# emitter.net
KiCad netlist of a schematic drawn in EAGLE
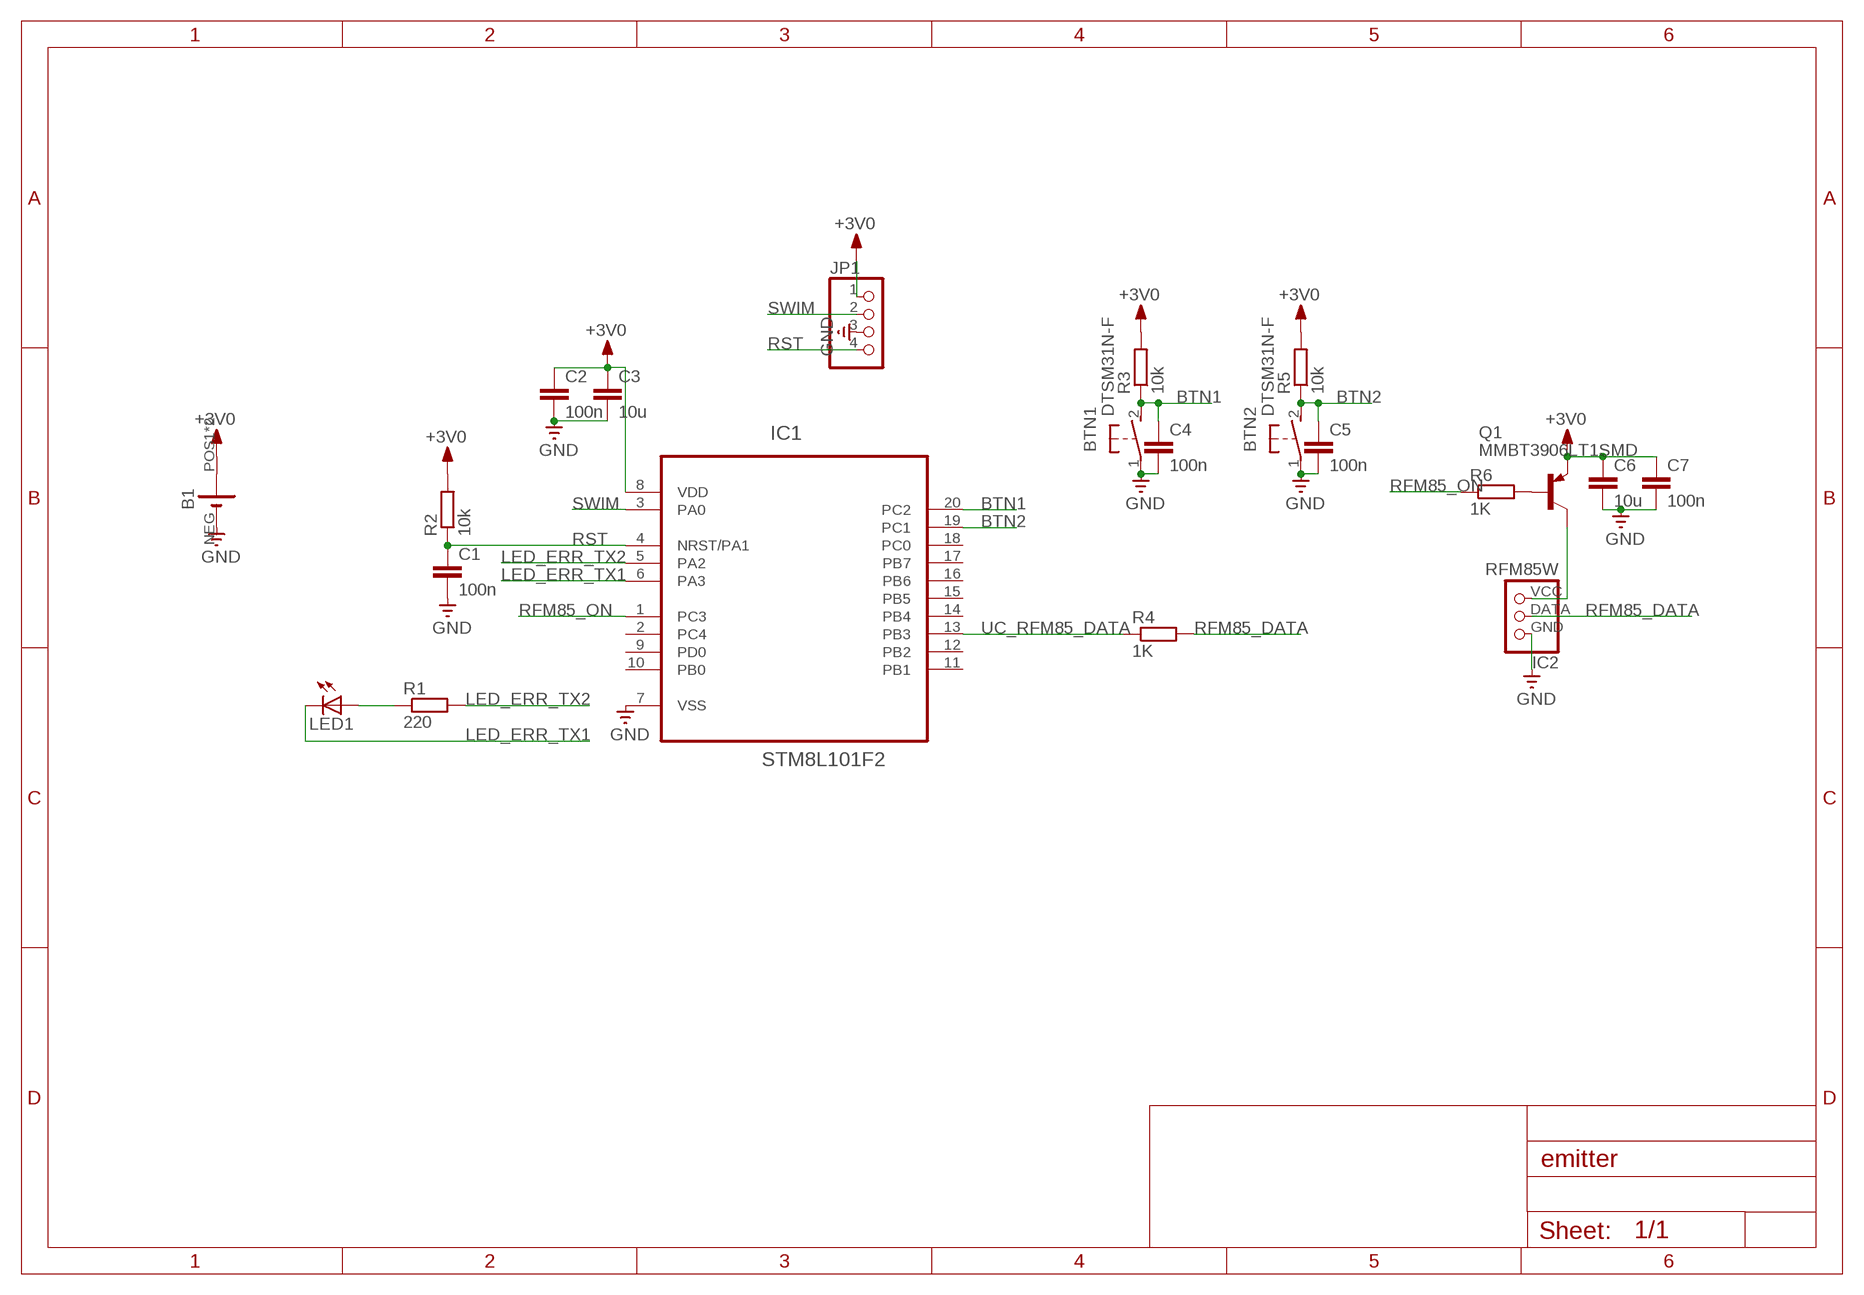
[diagram p0: schematic, sheet 1]

(export (version "E")
  (design (tool "Eeschema 10.0.6"))
  (components
    (comp (ref "B1")
      (value "CR2032_HOLDER_BC-2003")
      (footprint "eagle-import:CR2032_HOLDER_BC-2003")
      (libsource (lib "eagle-import") (part "CR2032_HOLDER_BC-2003"))
    )
    (comp (ref "BTN1")
      (value "DTSM31N-F")
      (footprint "eagle-import:DTSM31N-F")
      (libsource (lib "eagle-import") (part "DTSM31N-F"))
    )
    (comp (ref "BTN2")
      (value "DTSM31N-F")
      (footprint "eagle-import:DTSM31N-F")
      (libsource (lib "eagle-import") (part "DTSM31N-F"))
    )
    (comp (ref "C1")
      (value "100n")
      (footprint "eagle-import:C0603K")
      (libsource (lib "eagle-import") (part "C-EUC0603K"))
    )
    (comp (ref "C2")
      (value "100n")
      (footprint "eagle-import:C0603K")
      (libsource (lib "eagle-import") (part "C-EUC0603K"))
    )
    (comp (ref "C3")
      (value "10u")
      (footprint "eagle-import:C0805K")
      (libsource (lib "eagle-import") (part "C-EUC0805K"))
    )
    (comp (ref "C4")
      (value "100n")
      (footprint "eagle-import:C0603K")
      (libsource (lib "eagle-import") (part "C-EUC0603K"))
    )
    (comp (ref "C5")
      (value "100n")
      (footprint "eagle-import:C0603K")
      (libsource (lib "eagle-import") (part "C-EUC0603K"))
    )
    (comp (ref "C6")
      (value "10u")
      (footprint "eagle-import:C0805K")
      (libsource (lib "eagle-import") (part "C-EUC0805K"))
    )
    (comp (ref "C7")
      (value "100n")
      (footprint "eagle-import:C0603K")
      (libsource (lib "eagle-import") (part "C-EUC0603K"))
    )
    (comp (ref "IC1")
      (value "STM8L101F2")
      (footprint "eagle-import:TSSOP20")
      (libsource (lib "eagle-import") (part "STM8L101F2"))
    )
    (comp (ref "IC2")
      (value "RFM85W")
      (footprint "eagle-import:RFM85W_CON")
      (libsource (lib "eagle-import") (part "RFM85W"))
    )
    (comp (ref "JP1")
      (value "PINHD-1X4")
      (footprint "eagle-import:1X04")
      (libsource (lib "eagle-import") (part "PINHD-1X4"))
    )
    (comp (ref "LED1")
      (value "LED3MM")
      (footprint "eagle-import:LED3MM")
      (libsource (lib "eagle-import") (part "LED3MM"))
    )
    (comp (ref "Q1")
      (value "MMBT3906LT1SMD")
      (footprint "eagle-import:SOT23-BEC")
      (libsource (lib "eagle-import") (part "MMBT3906SMDLT1"))
    )
    (comp (ref "R1")
      (value "220")
      (footprint "eagle-import:R0603")
      (libsource (lib "eagle-import") (part "R-EU_R0603"))
    )
    (comp (ref "R2")
      (value "10k")
      (footprint "eagle-import:R0603")
      (libsource (lib "eagle-import") (part "R-EU_R0603"))
    )
    (comp (ref "R3")
      (value "10k")
      (footprint "eagle-import:R0603")
      (libsource (lib "eagle-import") (part "R-EU_R0603"))
    )
    (comp (ref "R4")
      (value "1K")
      (footprint "eagle-import:R0603")
      (libsource (lib "eagle-import") (part "R-EU_R0603"))
    )
    (comp (ref "R5")
      (value "10k")
      (footprint "eagle-import:R0603")
      (libsource (lib "eagle-import") (part "R-EU_R0603"))
    )
    (comp (ref "R6")
      (value "1K")
      (footprint "eagle-import:R0603")
      (libsource (lib "eagle-import") (part "R-EU_R0603"))
    )
  )
  (nets
    (net (code "1") (name "+3V0") (class "Default")
      (node (ref "B1") (pin "POS1") (pinfunction "+_POS1") (pintype "passive"))
      (node (ref "B1") (pin "POS2") (pinfunction "+_POS2") (pintype "passive"))
      (node (ref "C2") (pin "1") (pinfunction "1_1") (pintype "passive"))
      (node (ref "C3") (pin "1") (pinfunction "1_1") (pintype "passive"))
      (node (ref "C6") (pin "1") (pinfunction "1_1") (pintype "passive"))
      (node (ref "C7") (pin "1") (pinfunction "1_1") (pintype "passive"))
      (node (ref "IC1") (pin "8") (pinfunction "VDD_8") (pintype "power_in"))
      (node (ref "JP1") (pin "1") (pinfunction "1_1") (pintype "passive"))
      (node (ref "Q1") (pin "E") (pinfunction "E_E") (pintype "passive"))
      (node (ref "R2") (pin "2") (pinfunction "2_2") (pintype "passive"))
      (node (ref "R3") (pin "2") (pinfunction "2_2") (pintype "passive"))
      (node (ref "R5") (pin "2") (pinfunction "2_2") (pintype "passive"))
    )
    (net (code "2") (name "/BTN1") (class "Default")
      (node (ref "BTN1") (pin "2") (pinfunction "2_2") (pintype "passive"))
      (node (ref "C4") (pin "1") (pinfunction "1_1") (pintype "passive"))
      (node (ref "IC1") (pin "20") (pinfunction "PC2_20") (pintype "bidirectional"))
      (node (ref "R3") (pin "1") (pinfunction "1_1") (pintype "passive"))
    )
    (net (code "3") (name "/BTN2") (class "Default")
      (node (ref "BTN2") (pin "2") (pinfunction "2_2") (pintype "passive"))
      (node (ref "C5") (pin "1") (pinfunction "1_1") (pintype "passive"))
      (node (ref "IC1") (pin "19") (pinfunction "PC1_19") (pintype "bidirectional"))
      (node (ref "R5") (pin "1") (pinfunction "1_1") (pintype "passive"))
    )
    (net (code "4") (name "/LED_ERR_TX1") (class "Default")
      (node (ref "IC1") (pin "6") (pinfunction "PA3_6") (pintype "bidirectional"))
      (node (ref "LED1") (pin "K") (pinfunction "C_K") (pintype "passive"))
    )
    (net (code "5") (name "/LED_ERR_TX2") (class "Default")
      (node (ref "IC1") (pin "5") (pinfunction "PA2_5") (pintype "bidirectional"))
      (node (ref "R1") (pin "2") (pinfunction "2_2") (pintype "passive"))
    )
    (net (code "6") (name "/RFM85_DATA") (class "Default")
      (node (ref "IC2") (pin "DATA") (pinfunction "2_DATA") (pintype "passive"))
      (node (ref "R4") (pin "2") (pinfunction "2_2") (pintype "passive"))
    )
    (net (code "7") (name "/RFM85_ON") (class "Default")
      (node (ref "IC1") (pin "1") (pinfunction "PC3_1") (pintype "bidirectional"))
      (node (ref "R6") (pin "1") (pinfunction "1_1") (pintype "passive"))
    )
    (net (code "8") (name "/RST") (class "Default")
      (node (ref "C1") (pin "1") (pinfunction "1_1") (pintype "passive"))
      (node (ref "IC1") (pin "4") (pinfunction "NRST/PA1_4") (pintype "bidirectional"))
      (node (ref "JP1") (pin "4") (pinfunction "4_4") (pintype "passive"))
      (node (ref "R2") (pin "1") (pinfunction "1_1") (pintype "passive"))
    )
    (net (code "9") (name "/SWIM") (class "Default")
      (node (ref "IC1") (pin "3") (pinfunction "PA0_3") (pintype "power_in"))
      (node (ref "JP1") (pin "2") (pinfunction "2_2") (pintype "passive"))
    )
    (net (code "10") (name "/UC_RFM85_DATA") (class "Default")
      (node (ref "IC1") (pin "13") (pinfunction "PB3_13") (pintype "bidirectional"))
      (node (ref "R4") (pin "1") (pinfunction "1_1") (pintype "passive"))
    )
    (net (code "11") (name "GND") (class "Default")
      (node (ref "B1") (pin "NEG") (pinfunction "-_NEG") (pintype "passive"))
      (node (ref "BTN1") (pin "1") (pinfunction "1_1") (pintype "passive"))
      (node (ref "BTN2") (pin "1") (pinfunction "1_1") (pintype "passive"))
      (node (ref "C1") (pin "2") (pinfunction "2_2") (pintype "passive"))
      (node (ref "C2") (pin "2") (pinfunction "2_2") (pintype "passive"))
      (node (ref "C3") (pin "2") (pinfunction "2_2") (pintype "passive"))
      (node (ref "C4") (pin "2") (pinfunction "2_2") (pintype "passive"))
      (node (ref "C5") (pin "2") (pinfunction "2_2") (pintype "passive"))
      (node (ref "C6") (pin "2") (pinfunction "2_2") (pintype "passive"))
      (node (ref "C7") (pin "2") (pinfunction "2_2") (pintype "passive"))
      (node (ref "IC1") (pin "7") (pinfunction "VSS_7") (pintype "power_in"))
      (node (ref "IC2") (pin "GND") (pinfunction "1_GND") (pintype "passive"))
      (node (ref "JP1") (pin "3") (pinfunction "3_3") (pintype "passive"))
    )
    (net (code "12") (name "Net-(IC2-3)") (class "Default")
      (node (ref "IC2") (pin "VCC") (pinfunction "3_VCC") (pintype "passive"))
      (node (ref "Q1") (pin "C") (pinfunction "C_C") (pintype "passive"))
    )
    (net (code "13") (name "Net-(LED1-PadA)") (class "Default")
      (node (ref "LED1") (pin "A") (pinfunction "A_A") (pintype "passive"))
      (node (ref "R1") (pin "1") (pinfunction "1_1") (pintype "passive"))
    )
    (net (code "14") (name "Net-(Q1-PadB)") (class "Default")
      (node (ref "Q1") (pin "B") (pinfunction "B_B") (pintype "passive"))
      (node (ref "R6") (pin "2") (pinfunction "2_2") (pintype "passive"))
    )
    (net (code "15") (name "unconnected-(IC1-PB0-Pad10)") (class "Default")
      (node (ref "IC1") (pin "10") (pinfunction "PB0_10") (pintype "bidirectional"))
    )
    (net (code "16") (name "unconnected-(IC1-PB1-Pad11)") (class "Default")
      (node (ref "IC1") (pin "11") (pinfunction "PB1_11") (pintype "bidirectional"))
    )
    (net (code "17") (name "unconnected-(IC1-PB2-Pad12)") (class "Default")
      (node (ref "IC1") (pin "12") (pinfunction "PB2_12") (pintype "bidirectional"))
    )
    (net (code "18") (name "unconnected-(IC1-PB4-Pad14)") (class "Default")
      (node (ref "IC1") (pin "14") (pinfunction "PB4_14") (pintype "bidirectional"))
    )
    (net (code "19") (name "unconnected-(IC1-PB5-Pad15)") (class "Default")
      (node (ref "IC1") (pin "15") (pinfunction "PB5_15") (pintype "bidirectional"))
    )
    (net (code "20") (name "unconnected-(IC1-PB6-Pad16)") (class "Default")
      (node (ref "IC1") (pin "16") (pinfunction "PB6_16") (pintype "bidirectional"))
    )
    (net (code "21") (name "unconnected-(IC1-PB7-Pad17)") (class "Default")
      (node (ref "IC1") (pin "17") (pinfunction "PB7_17") (pintype "bidirectional"))
    )
    (net (code "22") (name "unconnected-(IC1-PC0-Pad18)") (class "Default")
      (node (ref "IC1") (pin "18") (pinfunction "PC0_18") (pintype "bidirectional"))
    )
    (net (code "23") (name "unconnected-(IC1-PC4-Pad2)") (class "Default")
      (node (ref "IC1") (pin "2") (pinfunction "PC4_2") (pintype "bidirectional"))
    )
    (net (code "24") (name "unconnected-(IC1-PD0-Pad9)") (class "Default")
      (node (ref "IC1") (pin "9") (pinfunction "PD0_9") (pintype "bidirectional"))
    )
  )
)
